# IHM.net
KiCad netlist of a schematic drawn in Altium Designer
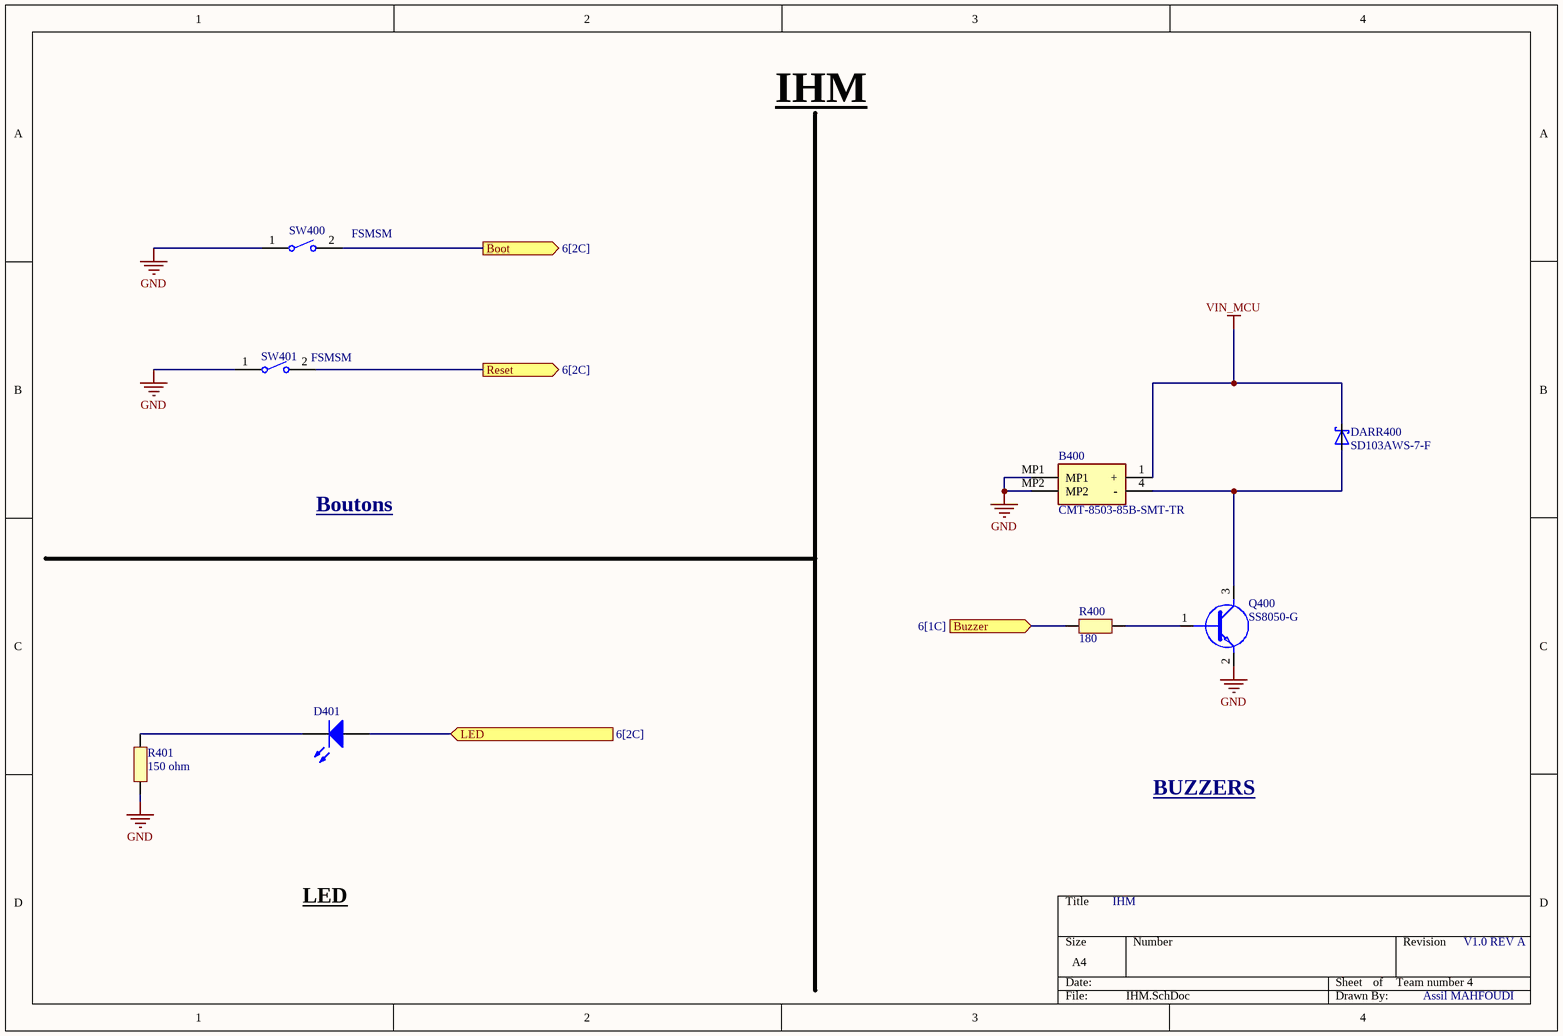
[diagram p0: IHM.SchDoc]

(export (version "E")
  (design (tool "Eeschema 10.0.6"))
  (components
    (comp (ref "B400")
      (value "CMT-8503-85B-SMT-TR")
      (footprint "CMT850385BSMTTR")
      (fields (field (name "MOUSER PART NUMBER") "490-CMT-850385BSMTTR"))
      (libsource (lib "SCHLibrary") (part "CMT-8503-85B-SMT-TR"))
    )
    (comp (ref "D401")
      (value "Light-Emitting Diode")
      (libsource (lib "Simulation Generic Components") (part "LED"))
    )
    (comp (ref "DARR400")
      (value "SD103AWS-7-F")
      (footprint "SD103AWS-7-F")
      (description "Diode Array 3 Independent Schottky 40V 175mA Surface Mount 6-TSSOP, SC-88, SOT-363")
      (libsource (lib "SCHLibrary") (part "SD103AWS-7-F"))
    )
    (comp (ref "Q400")
      (value "SS8050-G")
      (footprint "SS8050-G")
      (description "Bipolar Transistors - BJT NPN TRANSISTOR 1.5A 40V")
      (libsource (lib "SCHLibrary") (part "SS8050-G"))
    )
    (comp (ref "R400")
      (value "180")
      (footprint "RESC1005X06N")
      (libsource (lib "SCHLibrary") (part "Resistor"))
    )
    (comp (ref "R401") (value "150 ohm") (footprint "RESC1005X06N") (libsource (lib "") (part "Resistor_1")))
    (comp (ref "SW400")
      (value "FSMSM")
      (footprint "TECO-FSMSM-2_V")
      (description "FSMSM Push Button Switch, 50 mA, -35 to 85 degC, 2-Pin SMD, RoHS, Bulk")
      (fields (field (name "MANUFACTURER") "TE Connectivity"))
      (libsource (lib "SCHLibrary") (part "CMP-2000-07511-1"))
    )
    (comp (ref "SW401")
      (value "FSMSM")
      (footprint "TECO-FSMSM-2_V")
      (description "FSMSM Push Button Switch, 50 mA, -35 to 85 degC, 2-Pin SMD, RoHS, Bulk")
      (fields (field (name "MANUFACTURER") "TE Connectivity"))
      (libsource (lib "SCHLibrary") (part "CMP-2000-07511-1"))
    )
  )
  (nets
    (net (code "1") (name "/Boot") (class "Default")
      (node (ref "SW400") (pin "2") (pinfunction "2_2") (pintype "passive"))
    )
    (net (code "2") (name "/Buzzer") (class "Default")
      (node (ref "R400") (pin "1") (pinfunction "1_1") (pintype "passive"))
    )
    (net (code "3") (name "/LED") (class "Default")
      (node (ref "D401") (pin "1") (pinfunction "A_1") (pintype "passive"))
    )
    (net (code "4") (name "/Reset") (class "Default")
      (node (ref "SW401") (pin "2") (pinfunction "2_2") (pintype "passive"))
    )
    (net (code "5") (name "GND") (class "Default")
      (node (ref "B400") (pin "MP1") (pinfunction "MP1_MP1") (pintype "passive"))
      (node (ref "B400") (pin "MP2") (pinfunction "MP2_MP2") (pintype "passive"))
      (node (ref "Q400") (pin "2") (pinfunction "E_2") (pintype "passive"))
      (node (ref "R401") (pin "1") (pinfunction "1_1") (pintype "passive"))
      (node (ref "SW400") (pin "1") (pinfunction "1_1") (pintype "passive"))
      (node (ref "SW401") (pin "1") (pinfunction "1_1") (pintype "passive"))
    )
    (net (code "6") (name "Net-(B400--)") (class "Default")
      (node (ref "B400") (pin "4") (pinfunction "-_4") (pintype "passive"))
      (node (ref "DARR400") (pin "2") (pinfunction "A_2") (pintype "passive"))
      (node (ref "Q400") (pin "3") (pinfunction "C_3") (pintype "passive"))
    )
    (net (code "7") (name "Net-(D401-K)") (class "Default")
      (node (ref "D401") (pin "2") (pinfunction "K_2") (pintype "passive"))
      (node (ref "R401") (pin "2") (pinfunction "2_2") (pintype "passive"))
    )
    (net (code "8") (name "Net-(Q400-B)") (class "Default")
      (node (ref "Q400") (pin "1") (pinfunction "B_1") (pintype "passive"))
      (node (ref "R400") (pin "2") (pinfunction "2_2") (pintype "passive"))
    )
    (net (code "9") (name "VIN_MCU") (class "Default")
      (node (ref "B400") (pin "1") (pinfunction "+_1") (pintype "passive"))
      (node (ref "DARR400") (pin "1") (pinfunction "C_1") (pintype "passive"))
    )
  )
)
